# power-new-version.net
KiCad netlist of a schematic drawn in EAGLE
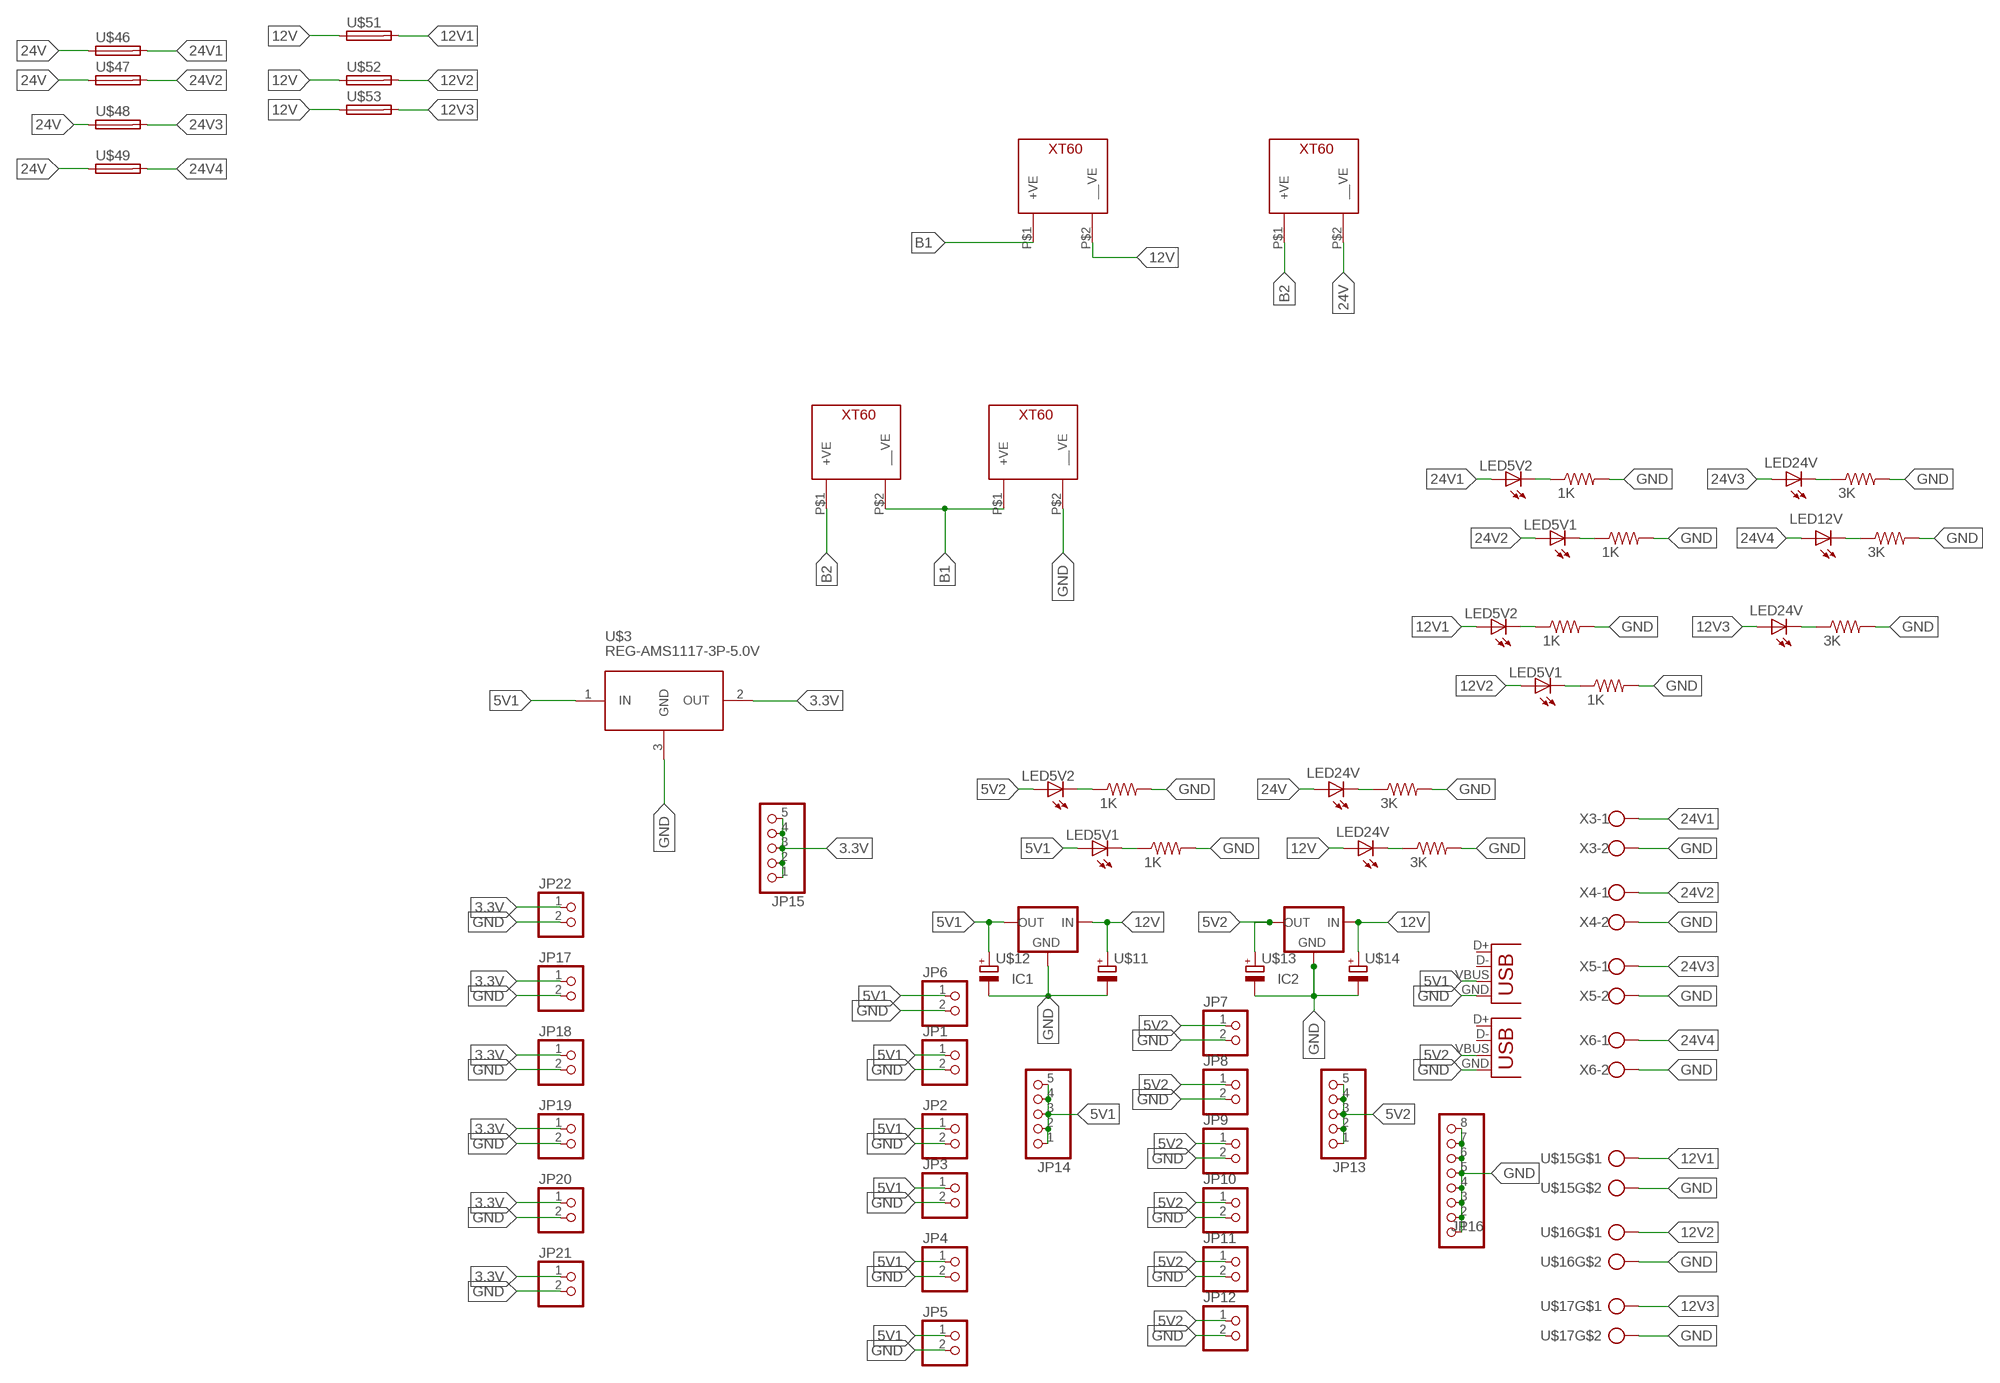
[diagram p0: schematic, sheet 1]

(export (version "E")
  (design (tool "Eeschema 10.0.6"))
  (components
    (comp (ref "1K")
      (value "1K")
      (footprint "eagle-import:0204_7")
      (libsource (lib "eagle-import") (part "RES-7"))
    )
    (comp (ref "1K1")
      (value "1K")
      (footprint "eagle-import:0204_7")
      (libsource (lib "eagle-import") (part "RES-7"))
    )
    (comp (ref "1K2")
      (value "1K")
      (footprint "eagle-import:0204_7")
      (libsource (lib "eagle-import") (part "RES-7"))
    )
    (comp (ref "IC1")
      (value "78XX-METAL")
      (footprint "eagle-import:TO3-79")
      (libsource (lib "eagle-import") (part "78XX-METAL"))
    )
    (comp (ref "IC2")
      (value "78XX-METAL")
      (footprint "eagle-import:TO3-79")
      (libsource (lib "eagle-import") (part "78XX-METAL"))
    )
    (comp (ref "JP1")
      (value "PINHD-2_DATA")
      (footprint "eagle-import:1X02_DATA")
      (libsource (lib "eagle-import") (part "PINHD-2_DATA"))
    )
    (comp (ref "JP2")
      (value "PINHD-2_DATA")
      (footprint "eagle-import:1X02_DATA")
      (libsource (lib "eagle-import") (part "PINHD-2_DATA"))
    )
    (comp (ref "JP3")
      (value "PINHD-2_DATA")
      (footprint "eagle-import:1X02_DATA")
      (libsource (lib "eagle-import") (part "PINHD-2_DATA"))
    )
    (comp (ref "JP4")
      (value "PINHD-2_DATA")
      (footprint "eagle-import:1X02_DATA")
      (libsource (lib "eagle-import") (part "PINHD-2_DATA"))
    )
    (comp (ref "JP5")
      (value "PINHD-2_DATA")
      (footprint "eagle-import:1X02_DATA")
      (libsource (lib "eagle-import") (part "PINHD-2_DATA"))
    )
    (comp (ref "JP6")
      (value "PINHD-2_DATA")
      (footprint "eagle-import:1X02_DATA")
      (libsource (lib "eagle-import") (part "PINHD-2_DATA"))
    )
    (comp (ref "JP7")
      (value "PINHD-2_DATA")
      (footprint "eagle-import:1X02_DATA")
      (libsource (lib "eagle-import") (part "PINHD-2_DATA"))
    )
    (comp (ref "JP8")
      (value "PINHD-2_DATA")
      (footprint "eagle-import:1X02_DATA")
      (libsource (lib "eagle-import") (part "PINHD-2_DATA"))
    )
    (comp (ref "JP9")
      (value "PINHD-2_DATA")
      (footprint "eagle-import:1X02_DATA")
      (libsource (lib "eagle-import") (part "PINHD-2_DATA"))
    )
    (comp (ref "JP10")
      (value "PINHD-2_DATA")
      (footprint "eagle-import:1X02_DATA")
      (libsource (lib "eagle-import") (part "PINHD-2_DATA"))
    )
    (comp (ref "JP11")
      (value "PINHD-2_DATA")
      (footprint "eagle-import:1X02_DATA")
      (libsource (lib "eagle-import") (part "PINHD-2_DATA"))
    )
    (comp (ref "JP12")
      (value "PINHD-2_DATA")
      (footprint "eagle-import:1X02_DATA")
      (libsource (lib "eagle-import") (part "PINHD-2_DATA"))
    )
    (comp (ref "JP13")
      (value "PINHD-1X5")
      (footprint "eagle-import:1X05")
      (libsource (lib "eagle-import") (part "PINHD-1X5"))
    )
    (comp (ref "JP14")
      (value "PINHD-1X5")
      (footprint "eagle-import:1X05")
      (libsource (lib "eagle-import") (part "PINHD-1X5"))
    )
    (comp (ref "JP15")
      (value "PINHD-1X5")
      (footprint "eagle-import:1X05")
      (libsource (lib "eagle-import") (part "PINHD-1X5"))
    )
    (comp (ref "JP16")
      (value "PINHD-1X8")
      (footprint "eagle-import:1X08")
      (libsource (lib "eagle-import") (part "PINHD-1X8"))
    )
    (comp (ref "JP17")
      (value "PINHD-2_DATA")
      (footprint "eagle-import:1X02_DATA")
      (libsource (lib "eagle-import") (part "PINHD-2_DATA"))
    )
    (comp (ref "JP18")
      (value "PINHD-2_DATA")
      (footprint "eagle-import:1X02_DATA")
      (libsource (lib "eagle-import") (part "PINHD-2_DATA"))
    )
    (comp (ref "JP19")
      (value "PINHD-2_DATA")
      (footprint "eagle-import:1X02_DATA")
      (libsource (lib "eagle-import") (part "PINHD-2_DATA"))
    )
    (comp (ref "JP20")
      (value "PINHD-2_DATA")
      (footprint "eagle-import:1X02_DATA")
      (libsource (lib "eagle-import") (part "PINHD-2_DATA"))
    )
    (comp (ref "JP21")
      (value "PINHD-2_DATA")
      (footprint "eagle-import:1X02_DATA")
      (libsource (lib "eagle-import") (part "PINHD-2_DATA"))
    )
    (comp (ref "JP22")
      (value "PINHD-2_DATA")
      (footprint "eagle-import:1X02_DATA")
      (libsource (lib "eagle-import") (part "PINHD-2_DATA"))
    )
    (comp (ref "U$1")
      (value "LED5V2")
      (footprint "eagle-import:LED3MM")
      (libsource (lib "eagle-import") (part "LED3MM"))
    )
    (comp (ref "U$2")
      (value "LED5V1")
      (footprint "eagle-import:LED3MM")
      (libsource (lib "eagle-import") (part "LED3MM"))
    )
    (comp (ref "U$3")
      (value "REG-AMS1117-3P-5.0V")
      (footprint "eagle-import:REG-AMS1117-3P")
      (libsource (lib "eagle-import") (part "REG-AMS1117-3P-5.0V"))
    )
    (comp (ref "U$4")
      (value "LED24V")
      (footprint "eagle-import:LED3MM")
      (libsource (lib "eagle-import") (part "LED3MM"))
    )
    (comp (ref "U$6")
      (value "XT60_CONNECTOR")
      (footprint "eagle-import:XT60")
      (libsource (lib "eagle-import") (part "XT60_CONNECTOR"))
    )
    (comp (ref "U$7")
      (value "1K")
      (footprint "eagle-import:0204_7")
      (libsource (lib "eagle-import") (part "RES-7"))
    )
    (comp (ref "U$8")
      (value "3K")
      (footprint "eagle-import:0204_7")
      (libsource (lib "eagle-import") (part "RES-7"))
    )
    (comp (ref "U$9")
      (value "3K")
      (footprint "eagle-import:0204_7")
      (libsource (lib "eagle-import") (part "RES-7"))
    )
    (comp (ref "U$10")
      (value "XT60_CONNECTOR")
      (footprint "eagle-import:XT60")
      (libsource (lib "eagle-import") (part "XT60_CONNECTOR"))
    )
    (comp (ref "U$11")
      (value "CAP_POL")
      (footprint "eagle-import:E3,5-8")
      (libsource (lib "eagle-import") (part "CAP_POL"))
    )
    (comp (ref "U$12")
      (value "CAP_POL")
      (footprint "eagle-import:E3,5-8")
      (libsource (lib "eagle-import") (part "CAP_POL"))
    )
    (comp (ref "U$13")
      (value "CAP_POL")
      (footprint "eagle-import:E3,5-8")
      (libsource (lib "eagle-import") (part "CAP_POL"))
    )
    (comp (ref "U$14")
      (value "CAP_POL")
      (footprint "eagle-import:E3,5-8")
      (libsource (lib "eagle-import") (part "CAP_POL"))
    )
    (comp (ref "U$15")
      (value "CON_PTR_2")
      (footprint "eagle-import:AK300_2")
      (libsource (lib "eagle-import") (part "CON_PTR_2"))
    )
    (comp (ref "U$16")
      (value "CON_PTR_2")
      (footprint "eagle-import:AK300_2")
      (libsource (lib "eagle-import") (part "CON_PTR_2"))
    )
    (comp (ref "U$17")
      (value "CON_PTR_2")
      (footprint "eagle-import:AK300_2")
      (libsource (lib "eagle-import") (part "CON_PTR_2"))
    )
    (comp (ref "U$18")
      (value "LED5V2")
      (footprint "eagle-import:LED3MM")
      (libsource (lib "eagle-import") (part "LED3MM"))
    )
    (comp (ref "U$19")
      (value "LED5V1")
      (footprint "eagle-import:LED3MM")
      (libsource (lib "eagle-import") (part "LED3MM"))
    )
    (comp (ref "U$20")
      (value "LED24V")
      (footprint "eagle-import:LED3MM")
      (libsource (lib "eagle-import") (part "LED3MM"))
    )
    (comp (ref "U$21")
      (value "LED12V")
      (footprint "eagle-import:LED3MM")
      (libsource (lib "eagle-import") (part "LED3MM"))
    )
    (comp (ref "U$22")
      (value "1K")
      (footprint "eagle-import:0204_7")
      (libsource (lib "eagle-import") (part "RES-7"))
    )
    (comp (ref "U$23")
      (value "3K")
      (footprint "eagle-import:0204_7")
      (libsource (lib "eagle-import") (part "RES-7"))
    )
    (comp (ref "U$24")
      (value "3K")
      (footprint "eagle-import:0204_7")
      (libsource (lib "eagle-import") (part "RES-7"))
    )
    (comp (ref "U$25")
      (value "LED5V2")
      (footprint "eagle-import:LED3MM")
      (libsource (lib "eagle-import") (part "LED3MM"))
    )
    (comp (ref "U$26")
      (value "LED5V1")
      (footprint "eagle-import:LED3MM")
      (libsource (lib "eagle-import") (part "LED3MM"))
    )
    (comp (ref "U$27")
      (value "LED24V")
      (footprint "eagle-import:LED3MM")
      (libsource (lib "eagle-import") (part "LED3MM"))
    )
    (comp (ref "U$28")
      (value "LED24V")
      (footprint "eagle-import:LED3MM")
      (libsource (lib "eagle-import") (part "LED3MM"))
    )
    (comp (ref "U$29")
      (value "1K")
      (footprint "eagle-import:0204_7")
      (libsource (lib "eagle-import") (part "RES-7"))
    )
    (comp (ref "U$31")
      (value "3K")
      (footprint "eagle-import:0204_7")
      (libsource (lib "eagle-import") (part "RES-7"))
    )
    (comp (ref "U$44")
      (value "XT60_CONNECTOR")
      (footprint "eagle-import:XT60")
      (libsource (lib "eagle-import") (part "XT60_CONNECTOR"))
    )
    (comp (ref "U$45")
      (value "XT60_CONNECTOR")
      (footprint "eagle-import:XT60")
      (libsource (lib "eagle-import") (part "XT60_CONNECTOR"))
    )
    (comp (ref "U$46")
      (value "FUSE_PANNEL_MOUNTPANEL_MOUNT")
      (footprint "eagle-import:PANEL_MOUNT")
      (libsource (lib "eagle-import") (part "FUSE_PANNEL_MOUNTPANEL_MOUNT"))
    )
    (comp (ref "U$47")
      (value "FUSE_PANNEL_MOUNTPANEL_MOUNT")
      (footprint "eagle-import:PANEL_MOUNT")
      (libsource (lib "eagle-import") (part "FUSE_PANNEL_MOUNTPANEL_MOUNT"))
    )
    (comp (ref "U$48")
      (value "FUSE_PANNEL_MOUNTPANEL_MOUNT")
      (footprint "eagle-import:PANEL_MOUNT")
      (libsource (lib "eagle-import") (part "FUSE_PANNEL_MOUNTPANEL_MOUNT"))
    )
    (comp (ref "U$49")
      (value "FUSE_PANNEL_MOUNTPANEL_MOUNT")
      (footprint "eagle-import:PANEL_MOUNT")
      (libsource (lib "eagle-import") (part "FUSE_PANNEL_MOUNTPANEL_MOUNT"))
    )
    (comp (ref "U$51")
      (value "FUSE_PANNEL_MOUNTPANEL_MOUNT")
      (footprint "eagle-import:PANEL_MOUNT")
      (libsource (lib "eagle-import") (part "FUSE_PANNEL_MOUNTPANEL_MOUNT"))
    )
    (comp (ref "U$52")
      (value "FUSE_PANNEL_MOUNTPANEL_MOUNT")
      (footprint "eagle-import:PANEL_MOUNT")
      (libsource (lib "eagle-import") (part "FUSE_PANNEL_MOUNTPANEL_MOUNT"))
    )
    (comp (ref "U$53")
      (value "FUSE_PANNEL_MOUNTPANEL_MOUNT")
      (footprint "eagle-import:PANEL_MOUNT")
      (libsource (lib "eagle-import") (part "FUSE_PANNEL_MOUNTPANEL_MOUNT"))
    )
    (comp (ref "X1")
      (value "USB-A-H")
      (footprint "eagle-import:USB-A-H")
      (libsource (lib "eagle-import") (part "USB-A-H"))
    )
    (comp (ref "X2")
      (value "USB-A-H")
      (footprint "eagle-import:USB-A-H")
      (libsource (lib "eagle-import") (part "USB-A-H"))
    )
    (comp (ref "X3")
      (value "ROSTA.POWER")
      (footprint "eagle-import:W239-302")
      (libsource (lib "eagle-import") (part "ROSTA.POWER"))
    )
    (comp (ref "X4")
      (value "ROSTA.POWER")
      (footprint "eagle-import:W239-302")
      (libsource (lib "eagle-import") (part "ROSTA.POWER"))
    )
    (comp (ref "X5")
      (value "ROSTA.POWER")
      (footprint "eagle-import:W239-302")
      (libsource (lib "eagle-import") (part "ROSTA.POWER"))
    )
    (comp (ref "X6")
      (value "ROSTA.POWER")
      (footprint "eagle-import:W239-302")
      (libsource (lib "eagle-import") (part "ROSTA.POWER"))
    )
  )
  (nets
    (net (code "1") (name "3.3V") (class "Default")
      (node (ref "JP15") (pin "1") (pinfunction "1_1") (pintype "passive"))
      (node (ref "JP15") (pin "2") (pinfunction "2_2") (pintype "passive"))
      (node (ref "JP15") (pin "3") (pinfunction "3_3") (pintype "passive"))
      (node (ref "JP15") (pin "4") (pinfunction "4_4") (pintype "passive"))
      (node (ref "JP15") (pin "5") (pinfunction "5_5") (pintype "passive"))
      (node (ref "JP17") (pin "1") (pinfunction "1_1") (pintype "passive"))
      (node (ref "JP18") (pin "1") (pinfunction "1_1") (pintype "passive"))
      (node (ref "JP19") (pin "1") (pinfunction "1_1") (pintype "passive"))
      (node (ref "JP20") (pin "1") (pinfunction "1_1") (pintype "passive"))
      (node (ref "JP21") (pin "1") (pinfunction "1_1") (pintype "passive"))
      (node (ref "JP22") (pin "1") (pinfunction "1_1") (pintype "passive"))
      (node (ref "U$3") (pin "2") (pinfunction "OUT_2") (pintype "bidirectional"))
    )
    (net (code "2") (name "5V1") (class "Default")
      (node (ref "IC1") (pin "1") (pinfunction "OUT_1") (pintype "passive"))
      (node (ref "JP1") (pin "1") (pinfunction "1_1") (pintype "passive"))
      (node (ref "JP14") (pin "1") (pinfunction "1_1") (pintype "passive"))
      (node (ref "JP14") (pin "2") (pinfunction "2_2") (pintype "passive"))
      (node (ref "JP14") (pin "3") (pinfunction "3_3") (pintype "passive"))
      (node (ref "JP14") (pin "4") (pinfunction "4_4") (pintype "passive"))
      (node (ref "JP14") (pin "5") (pinfunction "5_5") (pintype "passive"))
      (node (ref "JP2") (pin "1") (pinfunction "1_1") (pintype "passive"))
      (node (ref "JP3") (pin "1") (pinfunction "1_1") (pintype "passive"))
      (node (ref "JP4") (pin "1") (pinfunction "1_1") (pintype "passive"))
      (node (ref "JP5") (pin "1") (pinfunction "1_1") (pintype "passive"))
      (node (ref "JP6") (pin "1") (pinfunction "1_1") (pintype "passive"))
      (node (ref "U$12") (pin "+") (pinfunction "+_+") (pintype "passive"))
      (node (ref "U$2") (pin "A") (pinfunction "A_A") (pintype "passive"))
      (node (ref "U$3") (pin "1") (pinfunction "IN_1") (pintype "bidirectional"))
      (node (ref "X1") (pin "VBUS") (pinfunction "VBUS_VBUS") (pintype "bidirectional"))
    )
    (net (code "3") (name "5V2") (class "Default")
      (node (ref "IC2") (pin "1") (pinfunction "OUT_1") (pintype "passive"))
      (node (ref "JP10") (pin "1") (pinfunction "1_1") (pintype "passive"))
      (node (ref "JP11") (pin "1") (pinfunction "1_1") (pintype "passive"))
      (node (ref "JP12") (pin "1") (pinfunction "1_1") (pintype "passive"))
      (node (ref "JP13") (pin "1") (pinfunction "1_1") (pintype "passive"))
      (node (ref "JP13") (pin "2") (pinfunction "2_2") (pintype "passive"))
      (node (ref "JP13") (pin "3") (pinfunction "3_3") (pintype "passive"))
      (node (ref "JP13") (pin "4") (pinfunction "4_4") (pintype "passive"))
      (node (ref "JP13") (pin "5") (pinfunction "5_5") (pintype "passive"))
      (node (ref "JP7") (pin "1") (pinfunction "1_1") (pintype "passive"))
      (node (ref "JP8") (pin "1") (pinfunction "1_1") (pintype "passive"))
      (node (ref "JP9") (pin "1") (pinfunction "1_1") (pintype "passive"))
      (node (ref "U$1") (pin "A") (pinfunction "A_A") (pintype "passive"))
      (node (ref "U$13") (pin "+") (pinfunction "+_+") (pintype "passive"))
      (node (ref "X2") (pin "VBUS") (pinfunction "VBUS_VBUS") (pintype "bidirectional"))
    )
    (net (code "4") (name "12V") (class "Default")
      (node (ref "IC1") (pin "3") (pinfunction "IN_3") (pintype "input"))
      (node (ref "IC2") (pin "3") (pinfunction "IN_3") (pintype "input"))
      (node (ref "U$11") (pin "+") (pinfunction "+_+") (pintype "passive"))
      (node (ref "U$14") (pin "+") (pinfunction "+_+") (pintype "passive"))
      (node (ref "U$28") (pin "A") (pinfunction "A_A") (pintype "passive"))
      (node (ref "U$45") (pin "P$2") (pinfunction "__VE_P$2") (pintype "bidirectional"))
      (node (ref "U$51") (pin "P$1") (pinfunction "1_P$1") (pintype "passive"))
      (node (ref "U$52") (pin "P$1") (pinfunction "1_P$1") (pintype "passive"))
      (node (ref "U$53") (pin "P$1") (pinfunction "1_P$1") (pintype "passive"))
    )
    (net (code "5") (name "12V1") (class "Default")
      (node (ref "U$15") (pin "1") (pinfunction "KL_1") (pintype "passive"))
      (node (ref "U$25") (pin "A") (pinfunction "A_A") (pintype "passive"))
      (node (ref "U$51") (pin "P$2") (pinfunction "2_P$2") (pintype "passive"))
    )
    (net (code "6") (name "12V2") (class "Default")
      (node (ref "U$16") (pin "1") (pinfunction "KL_1") (pintype "passive"))
      (node (ref "U$26") (pin "A") (pinfunction "A_A") (pintype "passive"))
      (node (ref "U$52") (pin "P$2") (pinfunction "2_P$2") (pintype "passive"))
    )
    (net (code "7") (name "12V3") (class "Default")
      (node (ref "U$17") (pin "1") (pinfunction "KL_1") (pintype "passive"))
      (node (ref "U$27") (pin "A") (pinfunction "A_A") (pintype "passive"))
      (node (ref "U$53") (pin "P$2") (pinfunction "2_P$2") (pintype "passive"))
    )
    (net (code "8") (name "24V") (class "Default")
      (node (ref "U$4") (pin "A") (pinfunction "A_A") (pintype "passive"))
      (node (ref "U$44") (pin "P$2") (pinfunction "__VE_P$2") (pintype "bidirectional"))
      (node (ref "U$46") (pin "P$1") (pinfunction "1_P$1") (pintype "passive"))
      (node (ref "U$47") (pin "P$1") (pinfunction "1_P$1") (pintype "passive"))
      (node (ref "U$48") (pin "P$1") (pinfunction "1_P$1") (pintype "passive"))
      (node (ref "U$49") (pin "P$1") (pinfunction "1_P$1") (pintype "passive"))
    )
    (net (code "9") (name "24V1") (class "Default")
      (node (ref "U$18") (pin "A") (pinfunction "A_A") (pintype "passive"))
      (node (ref "U$46") (pin "P$2") (pinfunction "2_P$2") (pintype "passive"))
      (node (ref "X3") (pin "1") (pinfunction "KL_1") (pintype "passive"))
    )
    (net (code "10") (name "24V2") (class "Default")
      (node (ref "U$19") (pin "A") (pinfunction "A_A") (pintype "passive"))
      (node (ref "U$47") (pin "P$2") (pinfunction "2_P$2") (pintype "passive"))
      (node (ref "X4") (pin "1") (pinfunction "KL_1") (pintype "passive"))
    )
    (net (code "11") (name "24V3") (class "Default")
      (node (ref "U$20") (pin "A") (pinfunction "A_A") (pintype "passive"))
      (node (ref "U$48") (pin "P$2") (pinfunction "2_P$2") (pintype "passive"))
      (node (ref "X5") (pin "1") (pinfunction "KL_1") (pintype "passive"))
    )
    (net (code "12") (name "24V4") (class "Default")
      (node (ref "U$21") (pin "A") (pinfunction "A_A") (pintype "passive"))
      (node (ref "U$49") (pin "P$2") (pinfunction "2_P$2") (pintype "passive"))
      (node (ref "X6") (pin "1") (pinfunction "KL_1") (pintype "passive"))
    )
    (net (code "13") (name "B1") (class "Default")
      (node (ref "U$10") (pin "P$1") (pinfunction "+VE_P$1") (pintype "bidirectional"))
      (node (ref "U$45") (pin "P$1") (pinfunction "+VE_P$1") (pintype "bidirectional"))
      (node (ref "U$6") (pin "P$2") (pinfunction "__VE_P$2") (pintype "bidirectional"))
    )
    (net (code "14") (name "B2") (class "Default")
      (node (ref "U$44") (pin "P$1") (pinfunction "+VE_P$1") (pintype "bidirectional"))
      (node (ref "U$6") (pin "P$1") (pinfunction "+VE_P$1") (pintype "bidirectional"))
    )
    (net (code "15") (name "GND") (class "Default")
      (node (ref "1K") (pin "2") (pinfunction "2_2") (pintype "passive"))
      (node (ref "1K1") (pin "2") (pinfunction "2_2") (pintype "passive"))
      (node (ref "1K2") (pin "2") (pinfunction "2_2") (pintype "passive"))
      (node (ref "IC1") (pin "2") (pinfunction "GND_2") (pintype "input"))
      (node (ref "IC2") (pin "2") (pinfunction "GND_2") (pintype "input"))
      (node (ref "JP1") (pin "2") (pinfunction "2_2") (pintype "passive"))
      (node (ref "JP10") (pin "2") (pinfunction "2_2") (pintype "passive"))
      (node (ref "JP11") (pin "2") (pinfunction "2_2") (pintype "passive"))
      (node (ref "JP12") (pin "2") (pinfunction "2_2") (pintype "passive"))
      (node (ref "JP16") (pin "1") (pinfunction "1_1") (pintype "passive"))
      (node (ref "JP16") (pin "2") (pinfunction "2_2") (pintype "passive"))
      (node (ref "JP16") (pin "3") (pinfunction "3_3") (pintype "passive"))
      (node (ref "JP16") (pin "4") (pinfunction "4_4") (pintype "passive"))
      (node (ref "JP16") (pin "5") (pinfunction "5_5") (pintype "passive"))
      (node (ref "JP16") (pin "6") (pinfunction "6_6") (pintype "passive"))
      (node (ref "JP16") (pin "7") (pinfunction "7_7") (pintype "passive"))
      (node (ref "JP16") (pin "8") (pinfunction "8_8") (pintype "passive"))
      (node (ref "JP17") (pin "2") (pinfunction "2_2") (pintype "passive"))
      (node (ref "JP18") (pin "2") (pinfunction "2_2") (pintype "passive"))
      (node (ref "JP19") (pin "2") (pinfunction "2_2") (pintype "passive"))
      (node (ref "JP2") (pin "2") (pinfunction "2_2") (pintype "passive"))
      (node (ref "JP20") (pin "2") (pinfunction "2_2") (pintype "passive"))
      (node (ref "JP21") (pin "2") (pinfunction "2_2") (pintype "passive"))
      (node (ref "JP22") (pin "2") (pinfunction "2_2") (pintype "passive"))
      (node (ref "JP3") (pin "2") (pinfunction "2_2") (pintype "passive"))
      (node (ref "JP4") (pin "2") (pinfunction "2_2") (pintype "passive"))
      (node (ref "JP5") (pin "2") (pinfunction "2_2") (pintype "passive"))
      (node (ref "JP6") (pin "2") (pinfunction "2_2") (pintype "passive"))
      (node (ref "JP7") (pin "2") (pinfunction "2_2") (pintype "passive"))
      (node (ref "JP8") (pin "2") (pinfunction "2_2") (pintype "passive"))
      (node (ref "JP9") (pin "2") (pinfunction "2_2") (pintype "passive"))
      (node (ref "U$10") (pin "P$2") (pinfunction "__VE_P$2") (pintype "bidirectional"))
      (node (ref "U$11") (pin "-") (pinfunction "-_-") (pintype "passive"))
      (node (ref "U$12") (pin "-") (pinfunction "-_-") (pintype "passive"))
      (node (ref "U$13") (pin "-") (pinfunction "-_-") (pintype "passive"))
      (node (ref "U$14") (pin "-") (pinfunction "-_-") (pintype "passive"))
      (node (ref "U$15") (pin "2") (pinfunction "KL_2") (pintype "passive"))
      (node (ref "U$16") (pin "2") (pinfunction "KL_2") (pintype "passive"))
      (node (ref "U$17") (pin "2") (pinfunction "KL_2") (pintype "passive"))
      (node (ref "U$22") (pin "2") (pinfunction "2_2") (pintype "passive"))
      (node (ref "U$23") (pin "2") (pinfunction "2_2") (pintype "passive"))
      (node (ref "U$24") (pin "2") (pinfunction "2_2") (pintype "passive"))
      (node (ref "U$29") (pin "2") (pinfunction "2_2") (pintype "passive"))
      (node (ref "U$3") (pin "3") (pinfunction "GND_3") (pintype "bidirectional"))
      (node (ref "U$31") (pin "2") (pinfunction "2_2") (pintype "passive"))
      (node (ref "U$7") (pin "2") (pinfunction "2_2") (pintype "passive"))
      (node (ref "U$8") (pin "2") (pinfunction "2_2") (pintype "passive"))
      (node (ref "U$9") (pin "2") (pinfunction "2_2") (pintype "passive"))
      (node (ref "X1") (pin "GND") (pinfunction "GND_GND") (pintype "bidirectional"))
      (node (ref "X2") (pin "GND") (pinfunction "GND_GND") (pintype "bidirectional"))
      (node (ref "X3") (pin "2") (pinfunction "KL_2") (pintype "passive"))
      (node (ref "X4") (pin "2") (pinfunction "KL_2") (pintype "passive"))
      (node (ref "X5") (pin "2") (pinfunction "KL_2") (pintype "passive"))
      (node (ref "X6") (pin "2") (pinfunction "KL_2") (pintype "passive"))
    )
    (net (code "16") (name "Net-(U$1-C)") (class "Default")
      (node (ref "1K") (pin "1") (pinfunction "1_1") (pintype "passive"))
      (node (ref "U$1") (pin "K") (pinfunction "C_K") (pintype "passive"))
    )
    (net (code "17") (name "Net-(U$2-C)") (class "Default")
      (node (ref "U$2") (pin "K") (pinfunction "C_K") (pintype "passive"))
      (node (ref "U$7") (pin "1") (pinfunction "1_1") (pintype "passive"))
    )
    (net (code "18") (name "Net-(U$4-C)") (class "Default")
      (node (ref "U$4") (pin "K") (pinfunction "C_K") (pintype "passive"))
      (node (ref "U$9") (pin "1") (pinfunction "1_1") (pintype "passive"))
    )
    (net (code "19") (name "Net-(U$18-C)") (class "Default")
      (node (ref "1K1") (pin "1") (pinfunction "1_1") (pintype "passive"))
      (node (ref "U$18") (pin "K") (pinfunction "C_K") (pintype "passive"))
    )
    (net (code "20") (name "Net-(U$19-C)") (class "Default")
      (node (ref "U$19") (pin "K") (pinfunction "C_K") (pintype "passive"))
      (node (ref "U$22") (pin "1") (pinfunction "1_1") (pintype "passive"))
    )
    (net (code "21") (name "Net-(U$20-C)") (class "Default")
      (node (ref "U$20") (pin "K") (pinfunction "C_K") (pintype "passive"))
      (node (ref "U$24") (pin "1") (pinfunction "1_1") (pintype "passive"))
    )
    (net (code "22") (name "Net-(U$21-C)") (class "Default")
      (node (ref "U$21") (pin "K") (pinfunction "C_K") (pintype "passive"))
      (node (ref "U$23") (pin "1") (pinfunction "1_1") (pintype "passive"))
    )
    (net (code "23") (name "Net-(U$25-C)") (class "Default")
      (node (ref "1K2") (pin "1") (pinfunction "1_1") (pintype "passive"))
      (node (ref "U$25") (pin "K") (pinfunction "C_K") (pintype "passive"))
    )
    (net (code "24") (name "Net-(U$26-C)") (class "Default")
      (node (ref "U$26") (pin "K") (pinfunction "C_K") (pintype "passive"))
      (node (ref "U$29") (pin "1") (pinfunction "1_1") (pintype "passive"))
    )
    (net (code "25") (name "Net-(U$27-C)") (class "Default")
      (node (ref "U$27") (pin "K") (pinfunction "C_K") (pintype "passive"))
      (node (ref "U$31") (pin "1") (pinfunction "1_1") (pintype "passive"))
    )
    (net (code "26") (name "Net-(U$28-C)") (class "Default")
      (node (ref "U$28") (pin "K") (pinfunction "C_K") (pintype "passive"))
      (node (ref "U$8") (pin "1") (pinfunction "1_1") (pintype "passive"))
    )
    (net (code "27") (name "unconnected-(X1-PadD+)") (class "Default")
      (node (ref "X1") (pin "D+") (pinfunction "D+_D+") (pintype "bidirectional"))
    )
    (net (code "28") (name "unconnected-(X1-PadD-)") (class "Default")
      (node (ref "X1") (pin "D-") (pinfunction "D-_D-") (pintype "bidirectional"))
    )
    (net (code "29") (name "unconnected-(X2-PadD+)") (class "Default")
      (node (ref "X2") (pin "D+") (pinfunction "D+_D+") (pintype "bidirectional"))
    )
    (net (code "30") (name "unconnected-(X2-PadD-)") (class "Default")
      (node (ref "X2") (pin "D-") (pinfunction "D-_D-") (pintype "bidirectional"))
    )
  )
)
